# geiger2.net
KiCad netlist of a schematic drawn in EAGLE
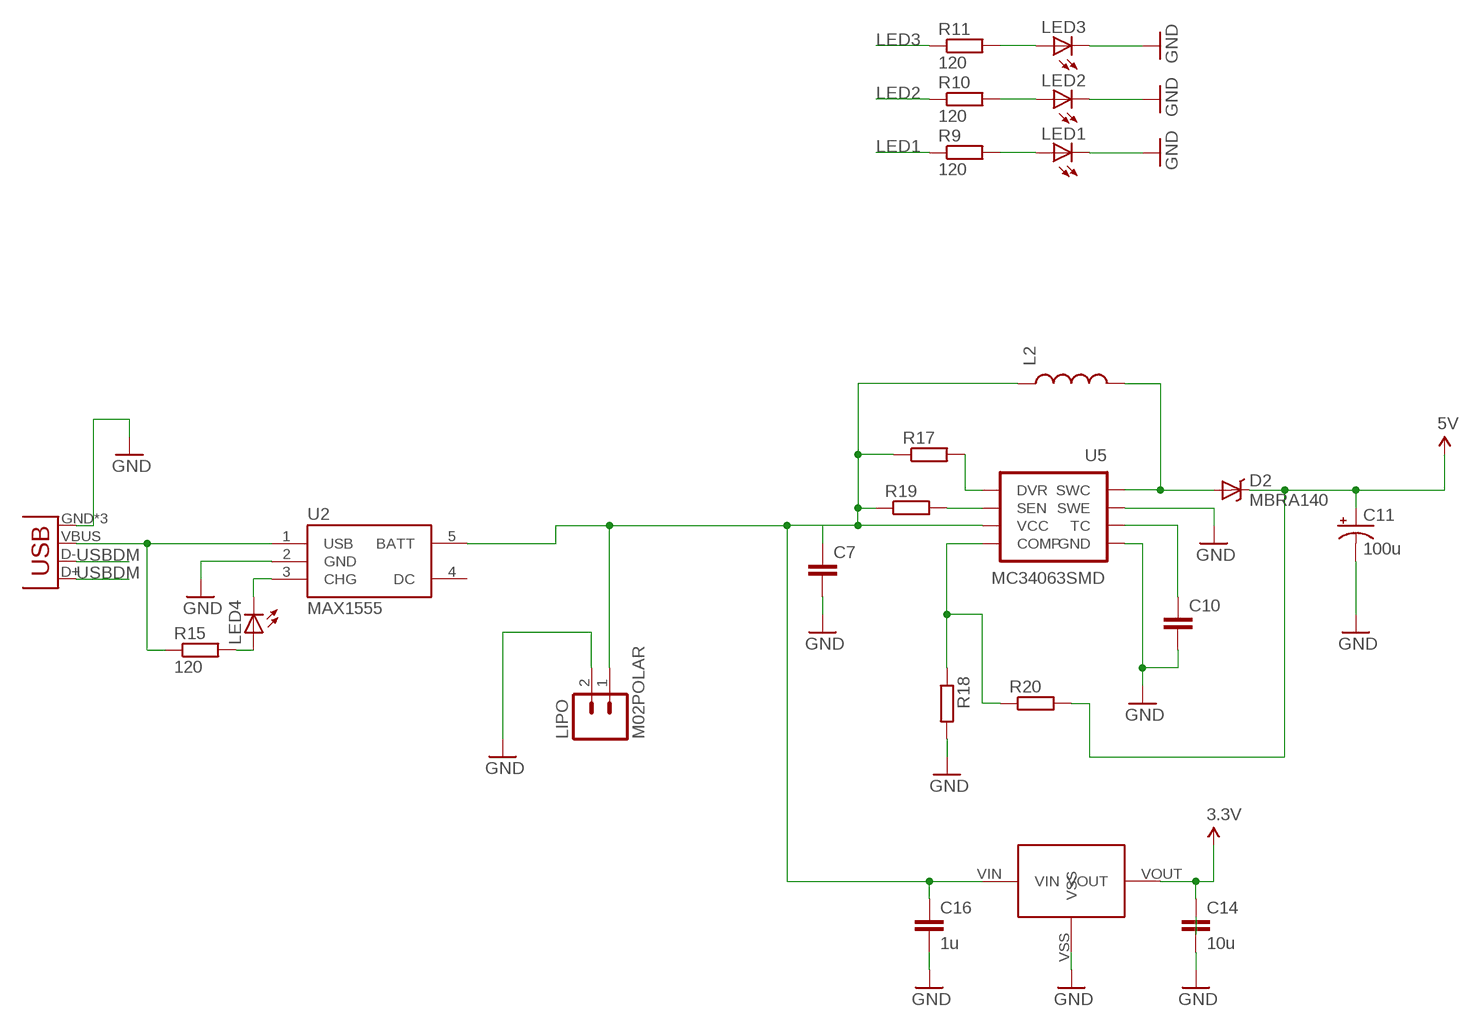
[diagram p0: schematic, sheet 1, part 1 of 2]
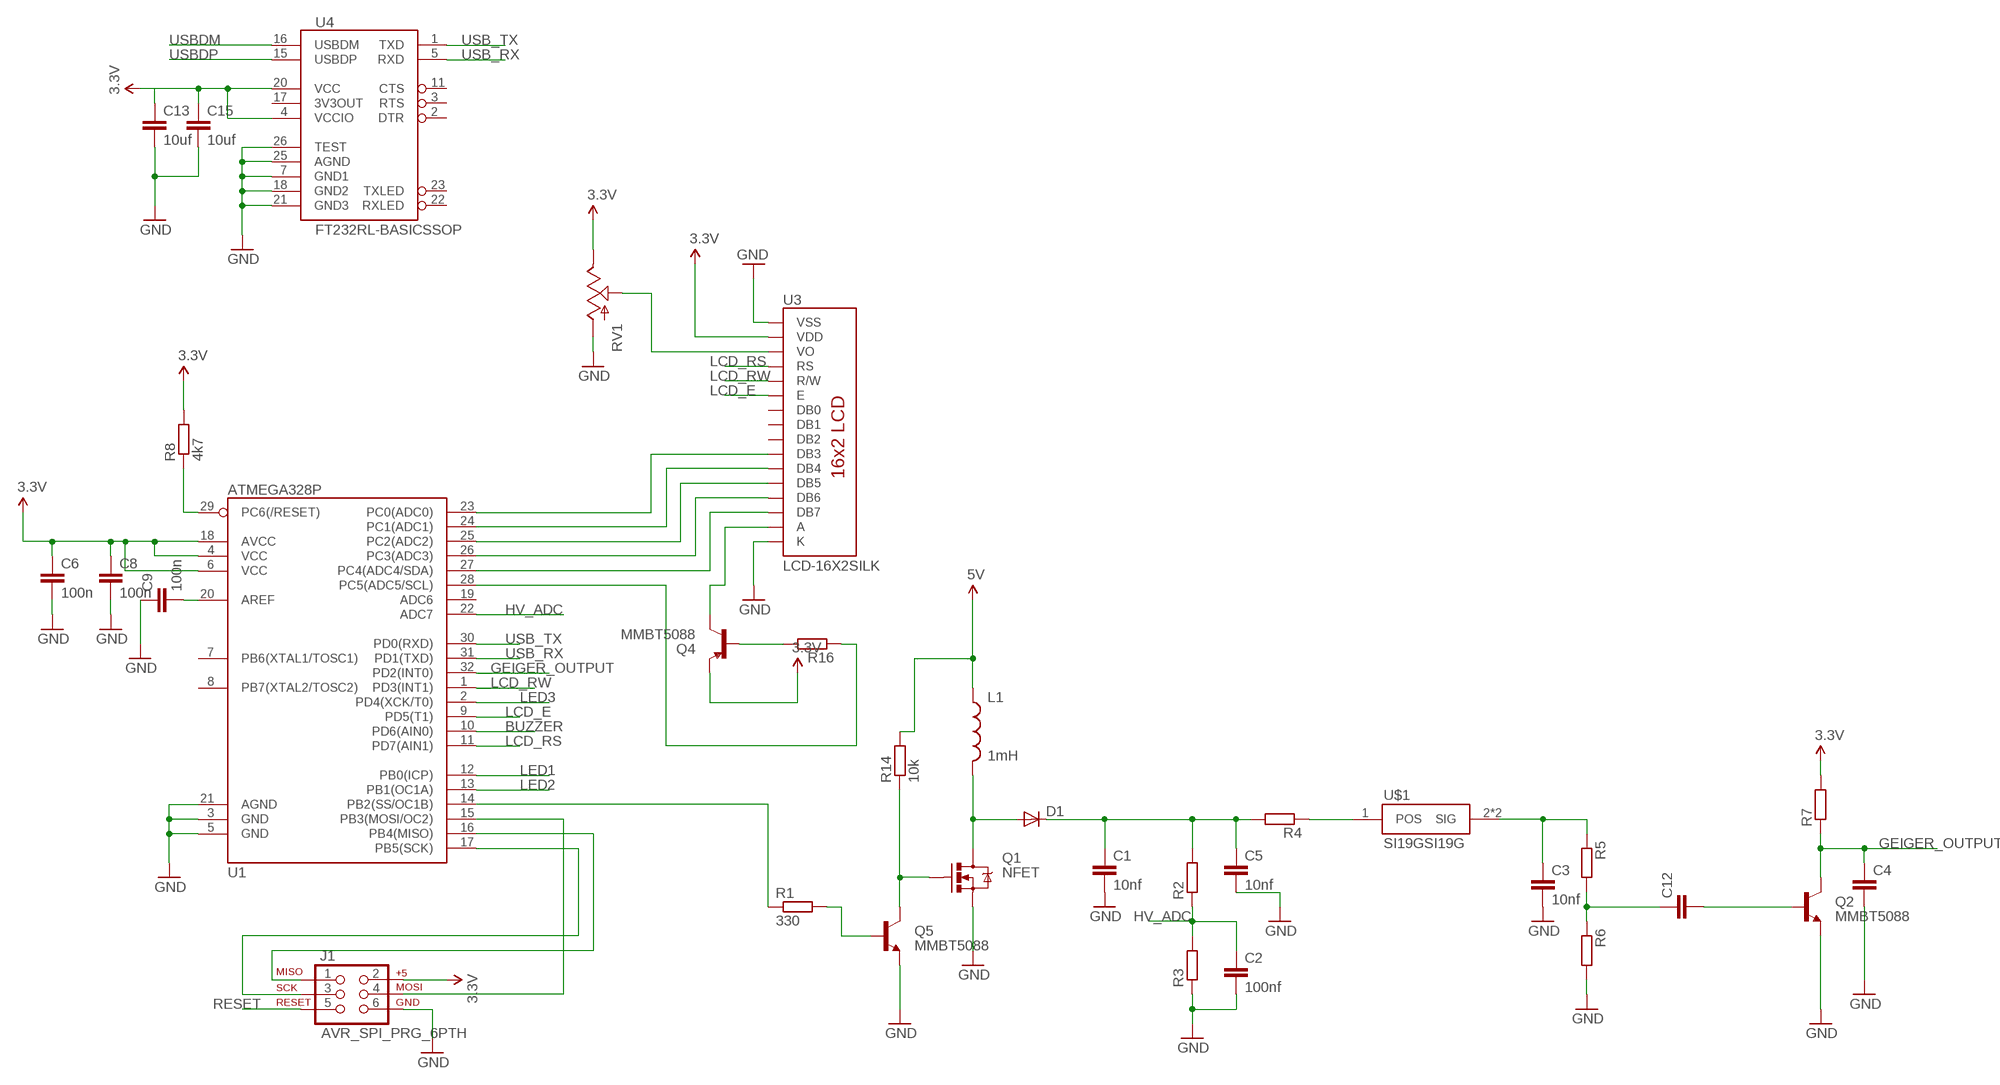
[diagram p1: schematic, sheet 1, part 2 of 2]

(export (version "E")
  (design (tool "Eeschema 10.0.6"))
  (components
    (comp (ref "C1")
      (value "10nf")
      (footprint "eagle-import:C075-032X103")
      (libsource (lib "eagle-import") (part "C-EU075-032X103"))
    )
    (comp (ref "C2")
      (value "100nf")
      (footprint "eagle-import:C0603")
      (libsource (lib "eagle-import") (part "C-EUC0603"))
    )
    (comp (ref "C3")
      (value "10nf")
      (footprint "eagle-import:C075-032X103")
      (libsource (lib "eagle-import") (part "C-EU075-032X103"))
    )
    (comp (ref "C4")
      (value "C-EUC0603")
      (footprint "eagle-import:C0603")
      (libsource (lib "eagle-import") (part "C-EUC0603"))
    )
    (comp (ref "C5")
      (value "10nf")
      (footprint "eagle-import:C075-032X103")
      (libsource (lib "eagle-import") (part "C-EU075-032X103"))
    )
    (comp (ref "C6")
      (value "100n")
      (footprint "eagle-import:C0603")
      (libsource (lib "eagle-import") (part "C-EUC0603"))
    )
    (comp (ref "C7")
      (value "C-EUC0805")
      (footprint "eagle-import:C0805")
      (libsource (lib "eagle-import") (part "C-EUC0805"))
    )
    (comp (ref "C8")
      (value "100n")
      (footprint "eagle-import:C0603")
      (libsource (lib "eagle-import") (part "C-EUC0603"))
    )
    (comp (ref "C9")
      (value "100n")
      (footprint "eagle-import:C0603")
      (libsource (lib "eagle-import") (part "C-EUC0603"))
    )
    (comp (ref "C10")
      (value "C-EUC0603")
      (footprint "eagle-import:C0603")
      (libsource (lib "eagle-import") (part "C-EUC0603"))
    )
    (comp (ref "C11")
      (value "100u")
      (footprint "eagle-import:NIPPON_F80")
      (libsource (lib "eagle-import") (part "CAP_POLF80"))
    )
    (comp (ref "C12")
      (value "C-EUC0603")
      (footprint "eagle-import:C0603")
      (libsource (lib "eagle-import") (part "C-EUC0603"))
    )
    (comp (ref "C13")
      (value "10uf")
      (footprint "eagle-import:C0603")
      (libsource (lib "eagle-import") (part "C-EUC0603"))
    )
    (comp (ref "C14")
      (value "10u")
      (footprint "eagle-import:C0603")
      (libsource (lib "eagle-import") (part "C-EUC0603"))
    )
    (comp (ref "C15")
      (value "10uf")
      (footprint "eagle-import:C0603")
      (libsource (lib "eagle-import") (part "C-EUC0603"))
    )
    (comp (ref "C16")
      (value "1u")
      (footprint "eagle-import:C0603")
      (libsource (lib "eagle-import") (part "C-EUC0603"))
    )
    (comp (ref "D1")
      (value "DIODEPTH")
      (footprint "eagle-import:DIODE-1N4001")
      (libsource (lib "eagle-import") (part "DIODEPTH"))
    )
    (comp (ref "D2")
      (value "MBRA140")
      (footprint "eagle-import:SMA-DIODE")
      (libsource (lib "eagle-import") (part "MBRA140"))
    )
    (comp (ref "J1")
      (value "AVR_SPI_PRG_6PTH")
      (footprint "eagle-import:2X3")
      (libsource (lib "eagle-import") (part "AVR_SPI_PRG_6PTH"))
    )
    (comp (ref "JP2")
      (value "USB-MICROB")
      (footprint "eagle-import:USB-MICROB")
      (libsource (lib "eagle-import") (part "USB-MICROB"))
    )
    (comp (ref "L1")
      (value "1mH")
      (footprint "eagle-import:RLB0912")
      (libsource (lib "eagle-import") (part "INDUCTORRLB0912"))
    )
    (comp (ref "L2")
      (value "INDUCTORCR75_V2")
      (footprint "eagle-import:CR75_V2")
      (libsource (lib "eagle-import") (part "INDUCTORCR75_V2"))
    )
    (comp (ref "LED1")
      (value "LED0603")
      (footprint "eagle-import:LED-0603")
      (libsource (lib "eagle-import") (part "LED0603"))
    )
    (comp (ref "LED2")
      (value "LED0603")
      (footprint "eagle-import:LED-0603")
      (libsource (lib "eagle-import") (part "LED0603"))
    )
    (comp (ref "LED3")
      (value "LED0603")
      (footprint "eagle-import:LED-0603")
      (libsource (lib "eagle-import") (part "LED0603"))
    )
    (comp (ref "LED4")
      (value "LED0603")
      (footprint "eagle-import:LED-0603")
      (libsource (lib "eagle-import") (part "LED0603"))
    )
    (comp (ref "LIPO")
      (value "M02POLAR")
      (footprint "eagle-import:MOLEX-1X2")
      (libsource (lib "eagle-import") (part "M02POLAR"))
    )
    (comp (ref "Q1")
      (value "NFET")
      (footprint "eagle-import:DPAK")
      (libsource (lib "eagle-import") (part "MOSFET-NCHANNELFDD8780"))
    )
    (comp (ref "Q2")
      (value "MMBT5088")
      (footprint "eagle-import:SOT23")
      (libsource (lib "eagle-import") (part "TRANSISTOR_NPNMMBT5088"))
    )
    (comp (ref "Q4")
      (value "MMBT5088")
      (footprint "eagle-import:SOT23-3")
      (libsource (lib "eagle-import") (part "TRANSISTOR_PNPSMD"))
    )
    (comp (ref "Q5")
      (value "MMBT5088")
      (footprint "eagle-import:SOT23")
      (libsource (lib "eagle-import") (part "TRANSISTOR_NPNMMBT5088"))
    )
    (comp (ref "R1")
      (value "330")
      (footprint "eagle-import:R0603")
      (libsource (lib "eagle-import") (part "R-EU_R0603"))
    )
    (comp (ref "R2")
      (value "R-EU_0207/10")
      (footprint "eagle-import:0207_10")
      (libsource (lib "eagle-import") (part "R-EU_0207/10"))
    )
    (comp (ref "R3")
      (value "R-EU_0207/10")
      (footprint "eagle-import:0207_10")
      (libsource (lib "eagle-import") (part "R-EU_0207/10"))
    )
    (comp (ref "R4")
      (value "R-EU_0207/10")
      (footprint "eagle-import:0207_10")
      (libsource (lib "eagle-import") (part "R-EU_0207/10"))
    )
    (comp (ref "R5")
      (value "R-EU_0207/10")
      (footprint "eagle-import:0207_10")
      (libsource (lib "eagle-import") (part "R-EU_0207/10"))
    )
    (comp (ref "R6")
      (value "R-EU_0207/10")
      (footprint "eagle-import:0207_10")
      (libsource (lib "eagle-import") (part "R-EU_0207/10"))
    )
    (comp (ref "R7")
      (value "R-EU_R0603")
      (footprint "eagle-import:R0603")
      (libsource (lib "eagle-import") (part "R-EU_R0603"))
    )
    (comp (ref "R8")
      (value "4k7")
      (footprint "eagle-import:R0603")
      (libsource (lib "eagle-import") (part "R-EU_R0603"))
    )
    (comp (ref "R9")
      (value "120")
      (footprint "eagle-import:R0603")
      (libsource (lib "eagle-import") (part "R-EU_R0603"))
    )
    (comp (ref "R10")
      (value "120")
      (footprint "eagle-import:R0603")
      (libsource (lib "eagle-import") (part "R-EU_R0603"))
    )
    (comp (ref "R11")
      (value "120")
      (footprint "eagle-import:R0603")
      (libsource (lib "eagle-import") (part "R-EU_R0603"))
    )
    (comp (ref "R14")
      (value "10k")
      (footprint "eagle-import:R0603")
      (libsource (lib "eagle-import") (part "R-EU_R0603"))
    )
    (comp (ref "R15")
      (value "120")
      (footprint "eagle-import:R0603")
      (libsource (lib "eagle-import") (part "R-EU_R0603"))
    )
    (comp (ref "R16")
      (value "R-EU_R0603")
      (footprint "eagle-import:R0603")
      (libsource (lib "eagle-import") (part "R-EU_R0603"))
    )
    (comp (ref "R17")
      (value "R-EU_R0603")
      (footprint "eagle-import:R0603")
      (libsource (lib "eagle-import") (part "R-EU_R0603"))
    )
    (comp (ref "R18")
      (value "R-EU_R0603")
      (footprint "eagle-import:R0603")
      (libsource (lib "eagle-import") (part "R-EU_R0603"))
    )
    (comp (ref "R19")
      (value "R-EU_R0603")
      (footprint "eagle-import:R0603")
      (libsource (lib "eagle-import") (part "R-EU_R0603"))
    )
    (comp (ref "R20")
      (value "R-EU_R0603")
      (footprint "eagle-import:R0603")
      (libsource (lib "eagle-import") (part "R-EU_R0603"))
    )
    (comp (ref "RV1")
      (value "POT100K_3362U")
      (footprint "eagle-import:3362U")
      (libsource (lib "eagle-import") (part "POT100K_3362U"))
    )
    (comp (ref "U$1")
      (value "SI19GSI19G")
      (footprint "eagle-import:SI19G")
      (libsource (lib "eagle-import") (part "SI19GSI19G"))
    )
    (comp (ref "U$2")
      (value "XC6026")
      (footprint "eagle-import:SOT23")
      (libsource (lib "eagle-import") (part "XC6026"))
    )
    (comp (ref "U1")
      (value "ATMEGA328P")
      (footprint "eagle-import:TQFP32-08")
      (libsource (lib "eagle-import") (part "ATMEGA328_SMT"))
    )
    (comp (ref "U2")
      (value "MAX1555")
      (footprint "eagle-import:SOT23-5")
      (libsource (lib "eagle-import") (part "MAX1555"))
    )
    (comp (ref "U3")
      (value "LCD-16X2SILK")
      (footprint "eagle-import:LCD-16X2")
      (libsource (lib "eagle-import") (part "LCD-16X2SILK"))
    )
    (comp (ref "U4")
      (value "FT232RL-BASICSSOP")
      (footprint "eagle-import:SSOP28DB")
      (libsource (lib "eagle-import") (part "FT232RL-BASICSSOP"))
    )
    (comp (ref "U5")
      (value "MC34063SMD")
      (footprint "eagle-import:SO08")
      (libsource (lib "eagle-import") (part "MC34063SMD"))
    )
  )
  (nets
    (net (code "1") (name "/BUZZER") (class "Default")
      (node (ref "U1") (pin "10") (pinfunction "PD6(AIN0)_10") (pintype "bidirectional"))
    )
    (net (code "2") (name "/GEIGER_OUTPUT") (class "Default")
      (node (ref "C4") (pin "1") (pinfunction "1_1") (pintype "passive"))
      (node (ref "Q2") (pin "3") (pinfunction "C_3") (pintype "passive"))
      (node (ref "R7") (pin "1") (pinfunction "1_1") (pintype "passive"))
      (node (ref "U1") (pin "32") (pinfunction "PD2(INT0)_32") (pintype "bidirectional"))
    )
    (net (code "3") (name "/HV_ADC") (class "Default")
      (node (ref "C2") (pin "1") (pinfunction "1_1") (pintype "passive"))
      (node (ref "R2") (pin "1") (pinfunction "1_1") (pintype "passive"))
      (node (ref "R3") (pin "2") (pinfunction "2_2") (pintype "passive"))
      (node (ref "U1") (pin "22") (pinfunction "ADC7_22") (pintype "bidirectional"))
    )
    (net (code "4") (name "/LCD_E") (class "Default")
      (node (ref "U1") (pin "9") (pinfunction "PD5(T1)_9") (pintype "bidirectional"))
      (node (ref "U3") (pin "6") (pinfunction "E_6") (pintype "input"))
    )
    (net (code "5") (name "/LCD_RS") (class "Default")
      (node (ref "U1") (pin "11") (pinfunction "PD7(AIN1)_11") (pintype "bidirectional"))
      (node (ref "U3") (pin "4") (pinfunction "RS_4") (pintype "input"))
    )
    (net (code "6") (name "/LCD_RW") (class "Default")
      (node (ref "U1") (pin "1") (pinfunction "PD3(INT1)_1") (pintype "bidirectional"))
      (node (ref "U3") (pin "5") (pinfunction "R/W_5") (pintype "input"))
    )
    (net (code "7") (name "/LED1") (class "Default")
      (node (ref "R9") (pin "1") (pinfunction "1_1") (pintype "passive"))
      (node (ref "U1") (pin "12") (pinfunction "PB0(ICP)_12") (pintype "bidirectional"))
    )
    (net (code "8") (name "/LED2") (class "Default")
      (node (ref "R10") (pin "1") (pinfunction "1_1") (pintype "passive"))
      (node (ref "U1") (pin "13") (pinfunction "PB1(OC1A)_13") (pintype "bidirectional"))
    )
    (net (code "9") (name "/LED3") (class "Default")
      (node (ref "R11") (pin "1") (pinfunction "1_1") (pintype "passive"))
      (node (ref "U1") (pin "2") (pinfunction "PD4(XCK/T0)_2") (pintype "bidirectional"))
    )
    (net (code "10") (name "/RESET") (class "Default")
      (node (ref "J1") (pin "5") (pinfunction "5_5") (pintype "passive"))
      (node (ref "R8") (pin "1") (pinfunction "1_1") (pintype "passive"))
      (node (ref "U1") (pin "29") (pinfunction "PC6(/RESET)_29") (pintype "bidirectional"))
    )
    (net (code "11") (name "/USBDM") (class "Default")
      (node (ref "JP2") (pin "D-") (pinfunction "D-_D-") (pintype "bidirectional"))
      (node (ref "U4") (pin "16") (pinfunction "USBDM_16") (pintype "bidirectional"))
    )
    (net (code "12") (name "/USBDP") (class "Default")
      (node (ref "JP2") (pin "D+") (pinfunction "D+_D+") (pintype "bidirectional"))
      (node (ref "U4") (pin "15") (pinfunction "USBDP_15") (pintype "bidirectional"))
    )
    (net (code "13") (name "/USB_RX") (class "Default")
      (node (ref "U1") (pin "31") (pinfunction "PD1(TXD)_31") (pintype "bidirectional"))
      (node (ref "U4") (pin "5") (pinfunction "RXD_5") (pintype "input"))
    )
    (net (code "14") (name "/USB_TX") (class "Default")
      (node (ref "U1") (pin "30") (pinfunction "PD0(RXD)_30") (pintype "bidirectional"))
      (node (ref "U4") (pin "1") (pinfunction "TXD_1") (pintype "output"))
    )
    (net (code "15") (name "3.3V") (class "Default")
      (node (ref "C13") (pin "1") (pinfunction "1_1") (pintype "passive"))
      (node (ref "C14") (pin "1") (pinfunction "1_1") (pintype "passive"))
      (node (ref "C15") (pin "1") (pinfunction "1_1") (pintype "passive"))
      (node (ref "C6") (pin "1") (pinfunction "1_1") (pintype "passive"))
      (node (ref "C8") (pin "1") (pinfunction "1_1") (pintype "passive"))
      (node (ref "J1") (pin "2") (pinfunction "2_2") (pintype "passive"))
      (node (ref "Q4") (pin "2") (pinfunction "E_2") (pintype "passive"))
      (node (ref "R7") (pin "2") (pinfunction "2_2") (pintype "passive"))
      (node (ref "R8") (pin "2") (pinfunction "2_2") (pintype "passive"))
      (node (ref "RV1") (pin "P$1") (pinfunction "E_P$1") (pintype "passive"))
      (node (ref "U$2") (pin "VOUT") (pinfunction "VOUT_VOUT") (pintype "bidirectional"))
      (node (ref "U1") (pin "18") (pinfunction "AVCC_18") (pintype "bidirectional"))
      (node (ref "U1") (pin "4") (pinfunction "VCC_4") (pintype "bidirectional"))
      (node (ref "U1") (pin "6") (pinfunction "VCC_6") (pintype "bidirectional"))
      (node (ref "U3") (pin "2") (pinfunction "VDD_2") (pintype "power_in"))
      (node (ref "U4") (pin "20") (pinfunction "VCC_20") (pintype "power_in"))
      (node (ref "U4") (pin "4") (pinfunction "VCCIO_4") (pintype "power_in"))
    )
    (net (code "16") (name "5V") (class "Default")
      (node (ref "C11") (pin "+") (pinfunction "+_+") (pintype "passive"))
      (node (ref "D2") (pin "C") (pinfunction "C_C") (pintype "passive"))
      (node (ref "L1") (pin "1") (pinfunction "1_1") (pintype "passive"))
      (node (ref "R14") (pin "2") (pinfunction "2_2") (pintype "passive"))
      (node (ref "R20") (pin "2") (pinfunction "2_2") (pintype "passive"))
    )
    (net (code "17") (name "GND") (class "Default")
      (node (ref "C1") (pin "2") (pinfunction "2_2") (pintype "passive"))
      (node (ref "C10") (pin "2") (pinfunction "2_2") (pintype "passive"))
      (node (ref "C11") (pin "-") (pinfunction "-_-") (pintype "passive"))
      (node (ref "C13") (pin "2") (pinfunction "2_2") (pintype "passive"))
      (node (ref "C14") (pin "2") (pinfunction "2_2") (pintype "passive"))
      (node (ref "C15") (pin "2") (pinfunction "2_2") (pintype "passive"))
      (node (ref "C16") (pin "2") (pinfunction "2_2") (pintype "passive"))
      (node (ref "C2") (pin "2") (pinfunction "2_2") (pintype "passive"))
      (node (ref "C3") (pin "2") (pinfunction "2_2") (pintype "passive"))
      (node (ref "C4") (pin "2") (pinfunction "2_2") (pintype "passive"))
      (node (ref "C5") (pin "2") (pinfunction "2_2") (pintype "passive"))
      (node (ref "C6") (pin "2") (pinfunction "2_2") (pintype "passive"))
      (node (ref "C7") (pin "2") (pinfunction "2_2") (pintype "passive"))
      (node (ref "C8") (pin "2") (pinfunction "2_2") (pintype "passive"))
      (node (ref "C9") (pin "1") (pinfunction "1_1") (pintype "passive"))
      (node (ref "J1") (pin "6") (pinfunction "6_6") (pintype "passive"))
      (node (ref "JP2") (pin "GND") (pinfunction "GND_GND") (pintype "bidirectional"))
      (node (ref "JP2") (pin "MT1") (pinfunction "GND_MT1") (pintype "bidirectional"))
      (node (ref "JP2") (pin "MT2") (pinfunction "GND_MT2") (pintype "bidirectional"))
      (node (ref "LED1") (pin "C") (pinfunction "C_C") (pintype "passive"))
      (node (ref "LED2") (pin "C") (pinfunction "C_C") (pintype "passive"))
      (node (ref "LED3") (pin "C") (pinfunction "C_C") (pintype "passive"))
      (node (ref "LIPO") (pin "2") (pinfunction "2_2") (pintype "passive"))
      (node (ref "Q1") (pin "3") (pinfunction "S_3") (pintype "passive"))
      (node (ref "Q2") (pin "2") (pinfunction "E_2") (pintype "passive"))
      (node (ref "Q5") (pin "2") (pinfunction "E_2") (pintype "passive"))
      (node (ref "R18") (pin "2") (pinfunction "2_2") (pintype "passive"))
      (node (ref "R3") (pin "1") (pinfunction "1_1") (pintype "passive"))
      (node (ref "R6") (pin "2") (pinfunction "2_2") (pintype "passive"))
      (node (ref "RV1") (pin "P$3") (pinfunction "A_P$3") (pintype "passive"))
      (node (ref "U$2") (pin "VSS") (pinfunction "VSS_VSS") (pintype "bidirectional"))
      (node (ref "U1") (pin "21") (pinfunction "AGND_21") (pintype "bidirectional"))
      (node (ref "U1") (pin "3") (pinfunction "GND_3") (pintype "bidirectional"))
      (node (ref "U1") (pin "5") (pinfunction "GND_5") (pintype "bidirectional"))
      (node (ref "U2") (pin "2") (pinfunction "GND_2") (pintype "bidirectional"))
      (node (ref "U3") (pin "1") (pinfunction "VSS_1") (pintype "power_in"))
      (node (ref "U3") (pin "16") (pinfunction "K_16") (pintype "power_in"))
      (node (ref "U4") (pin "18") (pinfunction "GND2_18") (pintype "power_in"))
      (node (ref "U4") (pin "21") (pinfunction "GND3_21") (pintype "power_in"))
      (node (ref "U4") (pin "25") (pinfunction "AGND_25") (pintype "power_in"))
      (node (ref "U4") (pin "26") (pinfunction "TEST_26") (pintype "input"))
      (node (ref "U4") (pin "7") (pinfunction "GND1_7") (pintype "power_in"))
      (node (ref "U5") (pin "2") (pinfunction "SWE_2") (pintype "bidirectional"))
      (node (ref "U5") (pin "4") (pinfunction "GND_4") (pintype "bidirectional"))
    )
    (net (code "18") (name "Net-(C1-Pad1)") (class "Default")
      (node (ref "C1") (pin "1") (pinfunction "1_1") (pintype "passive"))
      (node (ref "C5") (pin "1") (pinfunction "1_1") (pintype "passive"))
      (node (ref "D1") (pin "C") (pinfunction "C_C") (pintype "passive"))
      (node (ref "R2") (pin "2") (pinfunction "2_2") (pintype "passive"))
      (node (ref "R4") (pin "2") (pinfunction "2_2") (pintype "passive"))
    )
    (net (code "19") (name "Net-(C3-Pad1)") (class "Default")
      (node (ref "C3") (pin "1") (pinfunction "1_1") (pintype "passive"))
      (node (ref "R5") (pin "1") (pinfunction "1_1") (pintype "passive"))
      (node (ref "U$1") (pin "2") (pinfunction "SIG_2") (pintype "bidirectional"))
      (node (ref "U$1") (pin "3") (pinfunction "SIG_3") (pintype "bidirectional"))
    )
    (net (code "20") (name "Net-(C12-Pad1)") (class "Default")
      (node (ref "C12") (pin "1") (pinfunction "1_1") (pintype "passive"))
      (node (ref "R5") (pin "2") (pinfunction "2_2") (pintype "passive"))
      (node (ref "R6") (pin "1") (pinfunction "1_1") (pintype "passive"))
    )
    (net (code "21") (name "Net-(L2-1)") (class "Default")
      (node (ref "C16") (pin "1") (pinfunction "1_1") (pintype "passive"))
      (node (ref "C7") (pin "1") (pinfunction "1_1") (pintype "passive"))
      (node (ref "L2") (pin "P$1") (pinfunction "1_P$1") (pintype "passive"))
      (node (ref "LIPO") (pin "1") (pinfunction "1_1") (pintype "passive"))
      (node (ref "R17") (pin "1") (pinfunction "1_1") (pintype "passive"))
      (node (ref "R19") (pin "1") (pinfunction "1_1") (pintype "passive"))
      (node (ref "U$2") (pin "VIN") (pinfunction "VIN_VIN") (pintype "bidirectional"))
      (node (ref "U2") (pin "5") (pinfunction "BATT_5") (pintype "bidirectional"))
      (node (ref "U5") (pin "6") (pinfunction "VCC_6") (pintype "bidirectional"))
    )
    (net (code "22") (name "Net-(L2-2)") (class "Default")
      (node (ref "D2") (pin "A") (pinfunction "A_A") (pintype "passive"))
      (node (ref "L2") (pin "P$2") (pinfunction "2_P$2") (pintype "passive"))
      (node (ref "U5") (pin "1") (pinfunction "SWC_1") (pintype "bidirectional"))
    )
    (net (code "23") (name "Net-(LED1-PadA)") (class "Default")
      (node (ref "LED1") (pin "A") (pinfunction "A_A") (pintype "passive"))
      (node (ref "R9") (pin "2") (pinfunction "2_2") (pintype "passive"))
    )
    (net (code "24") (name "Net-(LED2-PadA)") (class "Default")
      (node (ref "LED2") (pin "A") (pinfunction "A_A") (pintype "passive"))
      (node (ref "R10") (pin "2") (pinfunction "2_2") (pintype "passive"))
    )
    (net (code "25") (name "Net-(LED3-PadA)") (class "Default")
      (node (ref "LED3") (pin "A") (pinfunction "A_A") (pintype "passive"))
      (node (ref "R11") (pin "2") (pinfunction "2_2") (pintype "passive"))
    )
    (net (code "26") (name "Net-(LED4-PadA)") (class "Default")
      (node (ref "LED4") (pin "A") (pinfunction "A_A") (pintype "passive"))
      (node (ref "R15") (pin "2") (pinfunction "2_2") (pintype "passive"))
    )
    (net (code "27") (name "Net-(Q1-D)") (class "Default")
      (node (ref "D1") (pin "A") (pinfunction "A_A") (pintype "passive"))
      (node (ref "L1") (pin "2") (pinfunction "2_2") (pintype "passive"))
      (node (ref "Q1") (pin "4") (pinfunction "D_4") (pintype "passive"))
    )
    (net (code "28") (name "Net-(Q1-G)") (class "Default")
      (node (ref "Q1") (pin "1") (pinfunction "G_1") (pintype "passive"))
      (node (ref "Q5") (pin "3") (pinfunction "C_3") (pintype "passive"))
      (node (ref "R14") (pin "1") (pinfunction "1_1") (pintype "passive"))
    )
    (net (code "29") (name "Net-(Q2-B)") (class "Default")
      (node (ref "C12") (pin "2") (pinfunction "2_2") (pintype "passive"))
      (node (ref "Q2") (pin "1") (pinfunction "B_1") (pintype "passive"))
    )
    (net (code "30") (name "Net-(Q4-B)") (class "Default")
      (node (ref "Q4") (pin "1") (pinfunction "B_1") (pintype "passive"))
      (node (ref "R16") (pin "2") (pinfunction "2_2") (pintype "passive"))
    )
    (net (code "31") (name "Net-(Q4-C)") (class "Default")
      (node (ref "Q4") (pin "3") (pinfunction "C_3") (pintype "passive"))
      (node (ref "U3") (pin "15") (pinfunction "A_15") (pintype "power_in"))
    )
    (net (code "32") (name "Net-(Q5-B)") (class "Default")
      (node (ref "Q5") (pin "1") (pinfunction "B_1") (pintype "passive"))
      (node (ref "R1") (pin "2") (pinfunction "2_2") (pintype "passive"))
    )
    (net (code "33") (name "Net-(RV1-S)") (class "Default")
      (node (ref "RV1") (pin "P$2") (pinfunction "S_P$2") (pintype "passive"))
      (node (ref "U3") (pin "3") (pinfunction "VO_3") (pintype "bidirectional"))
    )
    (net (code "34") (name "Net-(U$1-POS)") (class "Default")
      (node (ref "R4") (pin "1") (pinfunction "1_1") (pintype "passive"))
      (node (ref "U$1") (pin "1") (pinfunction "POS_1") (pintype "bidirectional"))
    )
    (net (code "35") (name "Net-(U1-AREF)") (class "Default")
      (node (ref "C9") (pin "2") (pinfunction "2_2") (pintype "passive"))
      (node (ref "U1") (pin "20") (pinfunction "AREF_20") (pintype "bidirectional"))
    )
    (net (code "36") (name "Net-(U1-PB2(SS{slash}OC1B))") (class "Default")
      (node (ref "R1") (pin "1") (pinfunction "1_1") (pintype "passive"))
      (node (ref "U1") (pin "14") (pinfunction "PB2(SS/OC1B)_14") (pintype "bidirectional"))
    )
    (net (code "37") (name "Net-(U1-PB3(MOSI{slash}OC2))") (class "Default")
      (node (ref "J1") (pin "4") (pinfunction "4_4") (pintype "passive"))
      (node (ref "U1") (pin "15") (pinfunction "PB3(MOSI/OC2)_15") (pintype "bidirectional"))
    )
    (net (code "38") (name "Net-(U1-PB4(MISO))") (class "Default")
      (node (ref "J1") (pin "1") (pinfunction "1_1") (pintype "passive"))
      (node (ref "U1") (pin "16") (pinfunction "PB4(MISO)_16") (pintype "bidirectional"))
    )
    (net (code "39") (name "Net-(U1-PB5(SCK))") (class "Default")
      (node (ref "J1") (pin "3") (pinfunction "3_3") (pintype "passive"))
      (node (ref "U1") (pin "17") (pinfunction "PB5(SCK)_17") (pintype "bidirectional"))
    )
    (net (code "40") (name "Net-(U1-PC0(ADC0))") (class "Default")
      (node (ref "U1") (pin "23") (pinfunction "PC0(ADC0)_23") (pintype "bidirectional"))
      (node (ref "U3") (pin "10") (pinfunction "DB3_10") (pintype "bidirectional"))
    )
    (net (code "41") (name "Net-(U1-PC1(ADC1))") (class "Default")
      (node (ref "U1") (pin "24") (pinfunction "PC1(ADC1)_24") (pintype "bidirectional"))
      (node (ref "U3") (pin "11") (pinfunction "DB4_11") (pintype "bidirectional"))
    )
    (net (code "42") (name "Net-(U1-PC2(ADC2))") (class "Default")
      (node (ref "U1") (pin "25") (pinfunction "PC2(ADC2)_25") (pintype "bidirectional"))
      (node (ref "U3") (pin "12") (pinfunction "DB5_12") (pintype "bidirectional"))
    )
    (net (code "43") (name "Net-(U1-PC3(ADC3))") (class "Default")
      (node (ref "U1") (pin "26") (pinfunction "PC3(ADC3)_26") (pintype "bidirectional"))
      (node (ref "U3") (pin "13") (pinfunction "DB6_13") (pintype "bidirectional"))
    )
    (net (code "44") (name "Net-(U1-PC4(ADC4{slash}SDA))") (class "Default")
      (node (ref "U1") (pin "27") (pinfunction "PC4(ADC4/SDA)_27") (pintype "bidirectional"))
      (node (ref "U3") (pin "14") (pinfunction "DB7_14") (pintype "bidirectional"))
    )
    (net (code "45") (name "Net-(U1-PC5(ADC5{slash}SCL))") (class "Default")
      (node (ref "R16") (pin "1") (pinfunction "1_1") (pintype "passive"))
      (node (ref "U1") (pin "28") (pinfunction "PC5(ADC5/SCL)_28") (pintype "bidirectional"))
    )
    (net (code "46") (name "Net-(U2-CHG)") (class "Default")
      (node (ref "LED4") (pin "C") (pinfunction "C_C") (pintype "passive"))
      (node (ref "U2") (pin "3") (pinfunction "CHG_3") (pintype "bidirectional"))
    )
    (net (code "47") (name "Net-(U2-USB)") (class "Default")
      (node (ref "JP2") (pin "VBUS") (pinfunction "VBUS_VBUS") (pintype "bidirectional"))
      (node (ref "R15") (pin "1") (pinfunction "1_1") (pintype "passive"))
      (node (ref "U2") (pin "1") (pinfunction "USB_1") (pintype "bidirectional"))
    )
    (net (code "48") (name "Net-(U5-COMP)") (class "Default")
      (node (ref "R18") (pin "1") (pinfunction "1_1") (pintype "passive"))
      (node (ref "R20") (pin "1") (pinfunction "1_1") (pintype "passive"))
      (node (ref "U5") (pin "5") (pinfunction "COMP_5") (pintype "bidirectional"))
    )
    (net (code "49") (name "Net-(U5-DVR)") (class "Default")
      (node (ref "R17") (pin "2") (pinfunction "2_2") (pintype "passive"))
      (node (ref "U5") (pin "8") (pinfunction "DVR_8") (pintype "bidirectional"))
    )
    (net (code "50") (name "Net-(U5-SEN)") (class "Default")
      (node (ref "R19") (pin "2") (pinfunction "2_2") (pintype "passive"))
      (node (ref "U5") (pin "7") (pinfunction "SEN_7") (pintype "bidirectional"))
    )
    (net (code "51") (name "Net-(U5-TC)") (class "Default")
      (node (ref "C10") (pin "1") (pinfunction "1_1") (pintype "passive"))
      (node (ref "U5") (pin "3") (pinfunction "TC_3") (pintype "bidirectional"))
    )
    (net (code "52") (name "unconnected-(U1-ADC6-Pad19)") (class "Default")
      (node (ref "U1") (pin "19") (pinfunction "ADC6_19") (pintype "bidirectional"))
    )
    (net (code "53") (name "unconnected-(U1-PB6(XTAL1{slash}TOSC1)-Pad7)") (class "Default")
      (node (ref "U1") (pin "7") (pinfunction "PB6(XTAL1/TOSC1)_7") (pintype "bidirectional"))
    )
    (net (code "54") (name "unconnected-(U1-PB7(XTAL2{slash}TOSC2)-Pad8)") (class "Default")
      (node (ref "U1") (pin "8") (pinfunction "PB7(XTAL2/TOSC2)_8") (pintype "bidirectional"))
    )
    (net (code "55") (name "unconnected-(U2-DC-Pad4)") (class "Default")
      (node (ref "U2") (pin "4") (pinfunction "DC_4") (pintype "bidirectional"))
    )
    (net (code "56") (name "unconnected-(U3-DB0-Pad7)") (class "Default")
      (node (ref "U3") (pin "7") (pinfunction "DB0_7") (pintype "bidirectional"))
    )
    (net (code "57") (name "unconnected-(U3-DB1-Pad8)") (class "Default")
      (node (ref "U3") (pin "8") (pinfunction "DB1_8") (pintype "bidirectional"))
    )
    (net (code "58") (name "unconnected-(U3-DB2-Pad9)") (class "Default")
      (node (ref "U3") (pin "9") (pinfunction "DB2_9") (pintype "bidirectional"))
    )
    (net (code "59") (name "unconnected-(U4-3V3OUT-Pad17)") (class "Default")
      (node (ref "U4") (pin "17") (pinfunction "3V3OUT_17") (pintype "output"))
    )
    (net (code "60") (name "unconnected-(U4-CTS-Pad11)") (class "Default")
      (node (ref "U4") (pin "11") (pinfunction "CTS_11") (pintype "bidirectional"))
    )
    (net (code "61") (name "unconnected-(U4-DTR-Pad2)") (class "Default")
      (node (ref "U4") (pin "2") (pinfunction "DTR_2") (pintype "bidirectional"))
    )
    (net (code "62") (name "unconnected-(U4-RTS-Pad3)") (class "Default")
      (node (ref "U4") (pin "3") (pinfunction "RTS_3") (pintype "bidirectional"))
    )
    (net (code "63") (name "unconnected-(U4-RXLED-Pad22)") (class "Default")
      (node (ref "U4") (pin "22") (pinfunction "RXLED_22") (pintype "bidirectional"))
    )
    (net (code "64") (name "unconnected-(U4-TXLED-Pad23)") (class "Default")
      (node (ref "U4") (pin "23") (pinfunction "TXLED_23") (pintype "bidirectional"))
    )
  )
)
